# Drvenkar_Dario.net
KiCad netlist of a schematic drawn in Altium Designer
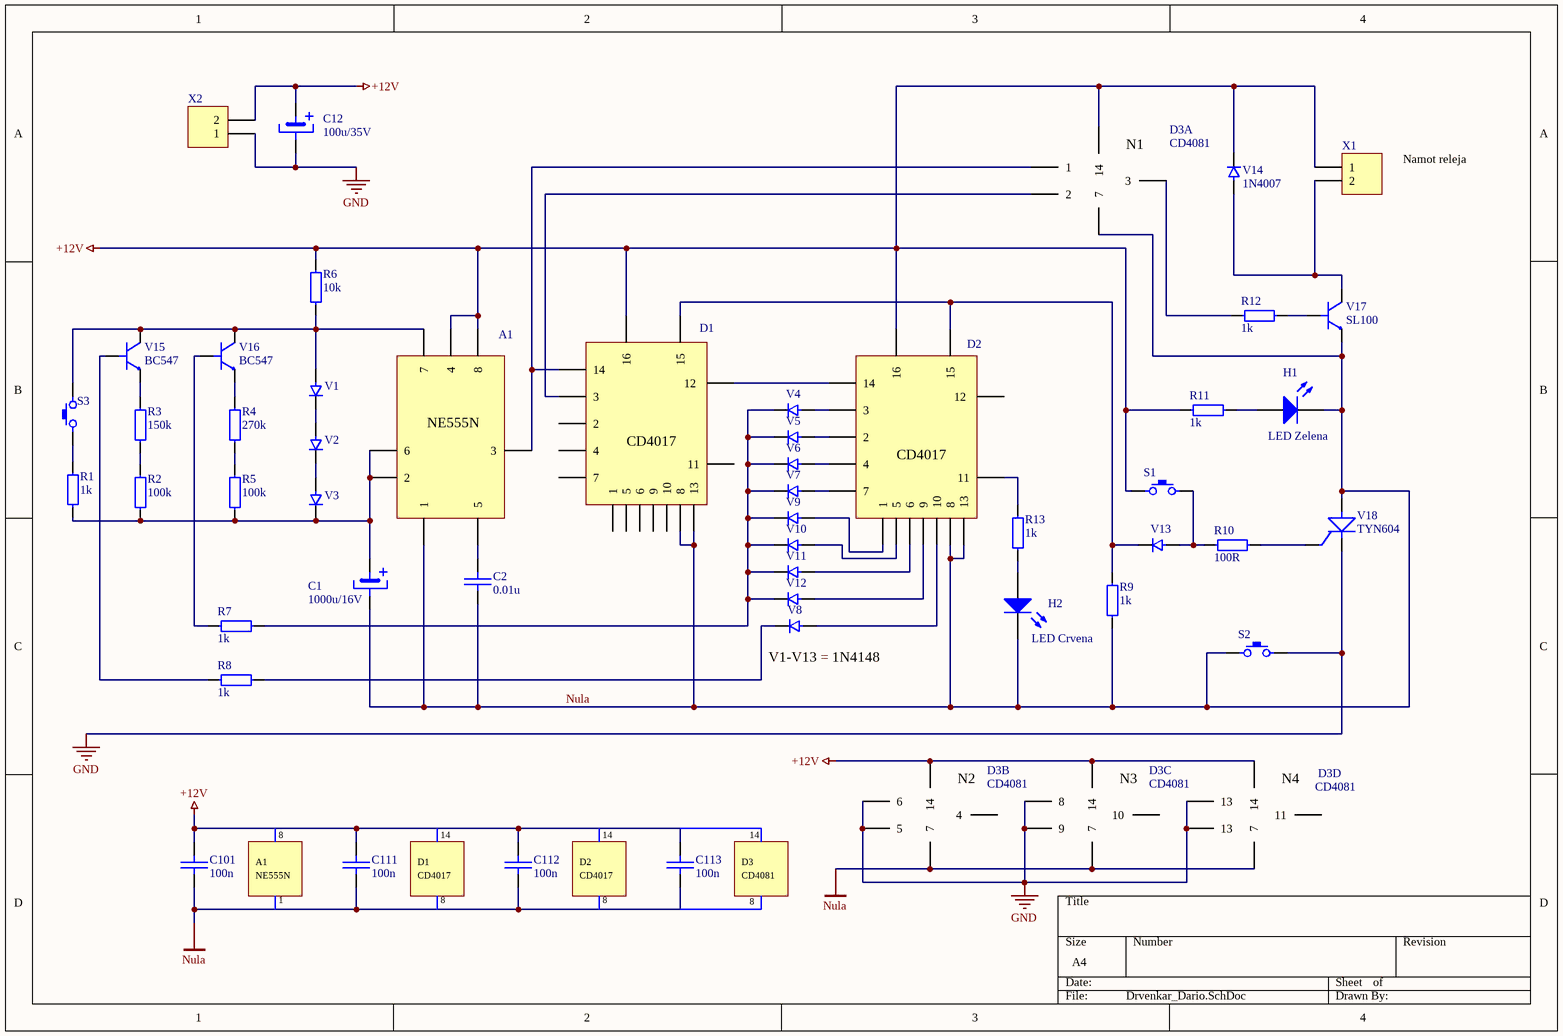
[diagram p0: Drvenkar_Dario.SchDoc]

(export (version "E")
  (design (tool "Eeschema 10.0.6"))
  (components
    (comp (ref "A1") (value "NE555N") (footprint "DIP-8") (libsource (lib "Schlib1") (part "NE555N")))
    (comp (ref "C1") (value "1000u/16V") (footprint "ELKO-10x16") (libsource (lib "Schlib1") (part "ELKO")))
    (comp (ref "C2") (value "0.01u") (footprint "RAD-0.2") (libsource (lib "Schlib1") (part "Kondenzator")))
    (comp (ref "C12")
      (value "100u/35V")
      (footprint "ELKO-6.3x20")
      (libsource (lib "Drvenkar_Dario") (part "ELKO"))
    )
    (comp (ref "C101") (value "100n") (footprint "RAD-0.2") (libsource (lib "Schlib1") (part "Kondenzator")))
    (comp (ref "C111") (value "100n") (footprint "RAD-0.2") (libsource (lib "Schlib1") (part "Kondenzator")))
    (comp (ref "C112") (value "100n") (footprint "RAD-0.2") (libsource (lib "Schlib1") (part "Kondenzator")))
    (comp (ref "C113") (value "100n") (footprint "RAD-0.2") (libsource (lib "Schlib1") (part "Kondenzator")))
    (comp (ref "D1") (value "CD4017") (footprint "DIP-16") (libsource (lib "Drvenkar_Dario") (part "CD4017")))
    (comp (ref "D2") (value "CD4017") (footprint "DIP-16") (libsource (lib "Drvenkar_Dario") (part "CD4017")))
    (comp (ref "D3") (value "CD4081") (footprint "DIP-14") (libsource (lib "Drvenkar_Dario") (part "CD4081")))
    (comp (ref "H1")
      (value "LED Zelena")
      (footprint "LED dioda")
      (description "Typical RED GaAs LED")
      (libsource (lib "Miscellaneous Devices") (part "LED1"))
    )
    (comp (ref "H2")
      (value "LED Crvena")
      (footprint "LED dioda")
      (description "Typical RED, GREEN, YELLOW, AMBER GaAs LED")
      (libsource (lib "Miscellaneous Devices") (part "LED2"))
    )
    (comp (ref "R1") (value "1k") (footprint "AXIAL-0.4") (libsource (lib "Schlib1") (part "Otpornik")))
    (comp (ref "R2") (value "100k") (footprint "AXIAL-0.4") (libsource (lib "Schlib1") (part "Otpornik")))
    (comp (ref "R3") (value "150k") (footprint "AXIAL-0.4") (libsource (lib "Schlib1") (part "Otpornik")))
    (comp (ref "R4") (value "270k") (footprint "AXIAL-0.4") (libsource (lib "Schlib1") (part "Otpornik")))
    (comp (ref "R5") (value "100k") (footprint "AXIAL-0.4") (libsource (lib "Schlib1") (part "Otpornik")))
    (comp (ref "R6") (value "10k") (footprint "AXIAL-0.4") (libsource (lib "Schlib1") (part "Otpornik")))
    (comp (ref "R7") (value "1k") (footprint "AXIAL-0.4") (libsource (lib "Schlib1") (part "Otpornik")))
    (comp (ref "R8") (value "1k") (footprint "AXIAL-0.4") (libsource (lib "Schlib1") (part "Otpornik")))
    (comp (ref "R9") (value "1k") (footprint "AXIAL-0.4") (libsource (lib "Schlib1") (part "Otpornik")))
    (comp (ref "R10") (value "100R") (footprint "AXIAL-0.4") (libsource (lib "Schlib1") (part "Otpornik")))
    (comp (ref "R11") (value "1k") (footprint "AXIAL-0.4") (libsource (lib "Schlib1") (part "Otpornik")))
    (comp (ref "R12") (value "1k") (footprint "AXIAL-0.4") (libsource (lib "Schlib1") (part "Otpornik")))
    (comp (ref "R13") (value "1k") (footprint "AXIAL-0.4") (libsource (lib "Schlib1") (part "Otpornik")))
    (comp (ref "S1") (value "Tipkalo") (footprint "Taster") (libsource (lib "Schlib1") (part "Tipkalo")))
    (comp (ref "S2") (value "Tipkalo") (footprint "Taster") (libsource (lib "Schlib1") (part "Tipkalo")))
    (comp (ref "S3") (value "Tipkalo") (footprint "Taster") (libsource (lib "") (part "Tipkalo_1")))
    (comp (ref "V1") (value "1N4148") (footprint "DIODE-0.4") (libsource (lib "Schlib1") (part "1N4148")))
    (comp (ref "V2") (value "1N4148") (footprint "DIODE-0.4") (libsource (lib "Schlib1") (part "1N4148")))
    (comp (ref "V3") (value "1N4148") (footprint "DIODE-0.4") (libsource (lib "Schlib1") (part "1N4148")))
    (comp (ref "V4") (value "1N4148") (footprint "DIODE-0.4") (libsource (lib "Schlib1") (part "1N4148")))
    (comp (ref "V5") (value "1N4148") (footprint "DIODE-0.4") (libsource (lib "Schlib1") (part "1N4148")))
    (comp (ref "V6") (value "1N4148") (footprint "DIODE-0.4") (libsource (lib "Schlib1") (part "1N4148")))
    (comp (ref "V7") (value "1N4148") (footprint "DIODE-0.4") (libsource (lib "Schlib1") (part "1N4148")))
    (comp (ref "V8") (value "1N4148") (footprint "DIODE-0.4") (libsource (lib "Schlib1") (part "1N4148")))
    (comp (ref "V9") (value "1N4148") (footprint "DIODE-0.4") (libsource (lib "Schlib1") (part "1N4148")))
    (comp (ref "V10") (value "1N4148") (footprint "DIODE-0.4") (libsource (lib "Schlib1") (part "1N4148")))
    (comp (ref "V11") (value "1N4148") (footprint "DIODE-0.4") (libsource (lib "Schlib1") (part "1N4148")))
    (comp (ref "V12") (value "1N4148") (footprint "DIODE-0.4") (libsource (lib "Schlib1") (part "1N4148")))
    (comp (ref "V13") (value "1N4148") (footprint "DIODE-0.4") (libsource (lib "Schlib1") (part "1N4148")))
    (comp (ref "V14") (value "1N4007") (footprint "DIODE-0.4") (libsource (lib "Schlib1") (part "1N4007")))
    (comp (ref "V15") (value "BC547") (footprint "TO-92") (libsource (lib "Schlib1") (part "Tranzistor")))
    (comp (ref "V16") (value "BC547") (footprint "TO-92") (libsource (lib "Schlib1") (part "Tranzistor")))
    (comp (ref "V17") (value "SL100") (footprint "TO-92") (libsource (lib "Schlib1") (part "Tranzistor")))
    (comp (ref "V18") (value "TYN604") (footprint "TO-220-AB") (libsource (lib "Schlib1") (part "Tiristor")))
    (comp (ref "X1")
      (value "2-pinski konektor")
      (footprint "Redna stezaljka")
      (description "Header, 2-Pin")
      (libsource (lib "Miscellaneous Connectors") (part "Header 2"))
    )
    (comp (ref "X2")
      (value "2-pinski konektor")
      (footprint "Redna stezaljka")
      (description "Header, 2-Pin")
      (libsource (lib "") (part "Header 2_1"))
    )
  )
  (nets
    (net (code "1") (name "+12V") (class "Default")
      (node (ref "A1") (pin "4") (pinfunction "4_4") (pintype "passive"))
      (node (ref "A1") (pin "8") (pinfunction "8_8") (pintype "passive"))
      (node (ref "C101") (pin "1") (pinfunction "1_1") (pintype "passive"))
      (node (ref "C111") (pin "1") (pinfunction "1_1") (pintype "passive"))
      (node (ref "C112") (pin "1") (pinfunction "1_1") (pintype "passive"))
      (node (ref "C113") (pin "1") (pinfunction "1_1") (pintype "passive"))
      (node (ref "C12") (pin "1") (pinfunction "1_1") (pintype "passive"))
      (node (ref "D1") (pin "16") (pinfunction "16_16") (pintype "passive"))
      (node (ref "D2") (pin "16") (pinfunction "16_16") (pintype "passive"))
      (node (ref "D3") (pin "14") (pinfunction "14_14") (pintype "passive"))
      (node (ref "R11") (pin "1") (pinfunction "1_1") (pintype "passive"))
      (node (ref "R6") (pin "1") (pinfunction "1_1") (pintype "passive"))
      (node (ref "S1") (pin "2") (pinfunction "2_2") (pintype "passive"))
      (node (ref "V14") (pin "2") (pinfunction "2_2") (pintype "passive"))
      (node (ref "X1") (pin "1") (pinfunction "1_1") (pintype "passive"))
      (node (ref "X2") (pin "2") (pinfunction "2_2") (pintype "passive"))
    )
    (net (code "2") (name "GND") (class "Default")
      (node (ref "C12") (pin "2") (pinfunction "2_2") (pintype "passive"))
      (node (ref "D3") (pin "13") (pinfunction "13_13") (pintype "passive"))
      (node (ref "D3") (pin "5") (pinfunction "5_5") (pintype "passive"))
      (node (ref "D3") (pin "6") (pinfunction "6_6") (pintype "passive"))
      (node (ref "D3") (pin "8") (pinfunction "8_8") (pintype "passive"))
      (node (ref "D3") (pin "9") (pinfunction "9_9") (pintype "passive"))
      (node (ref "S2") (pin "1") (pinfunction "1_1") (pintype "passive"))
      (node (ref "V18") (pin "2") (pinfunction "2_2") (pintype "passive"))
      (node (ref "X2") (pin "1") (pinfunction "1_1") (pintype "passive"))
    )
    (net (code "3") (name "Net-(A1-Pad2)") (class "Default")
      (node (ref "A1") (pin "2") (pinfunction "2_2") (pintype "passive"))
      (node (ref "A1") (pin "6") (pinfunction "6_6") (pintype "passive"))
      (node (ref "C1") (pin "1") (pinfunction "1_1") (pintype "passive"))
      (node (ref "R1") (pin "2") (pinfunction "2_2") (pintype "passive"))
      (node (ref "R2") (pin "2") (pinfunction "2_2") (pintype "passive"))
      (node (ref "R5") (pin "1") (pinfunction "1_1") (pintype "passive"))
      (node (ref "V3") (pin "2") (pinfunction "2_2") (pintype "passive"))
    )
    (net (code "4") (name "Net-(A1-Pad3)") (class "Default")
      (node (ref "A1") (pin "3") (pinfunction "3_3") (pintype "passive"))
      (node (ref "D1") (pin "14") (pinfunction "14_14") (pintype "passive"))
      (node (ref "D3") (pin "1") (pinfunction "1_1") (pintype "passive"))
    )
    (net (code "5") (name "Net-(A1-Pad5)") (class "Default")
      (node (ref "A1") (pin "5") (pinfunction "5_5") (pintype "passive"))
      (node (ref "C2") (pin "2") (pinfunction "2_2") (pintype "passive"))
    )
    (net (code "6") (name "Net-(A1-Pad7)") (class "Default")
      (node (ref "A1") (pin "7") (pinfunction "7_7") (pintype "passive"))
      (node (ref "R6") (pin "2") (pinfunction "2_2") (pintype "passive"))
      (node (ref "S3") (pin "1") (pinfunction "1_1") (pintype "passive"))
      (node (ref "V1") (pin "1") (pinfunction "1_1") (pintype "passive"))
      (node (ref "V15") (pin "3") (pinfunction "3_3") (pintype "passive"))
      (node (ref "V16") (pin "3") (pinfunction "3_3") (pintype "passive"))
    )
    (net (code "7") (name "Net-(D1-Pad3)") (class "Default")
      (node (ref "D1") (pin "3") (pinfunction "3_3") (pintype "passive"))
      (node (ref "D3") (pin "2") (pinfunction "2_2") (pintype "passive"))
    )
    (net (code "8") (name "Net-(D1-Pad12)") (class "Default")
      (node (ref "D1") (pin "12") (pinfunction "12_12") (pintype "passive"))
      (node (ref "D2") (pin "14") (pinfunction "14_14") (pintype "passive"))
    )
    (net (code "9") (name "Net-(D1-Pad15)") (class "Default")
      (node (ref "D1") (pin "15") (pinfunction "15_15") (pintype "passive"))
      (node (ref "D2") (pin "15") (pinfunction "15_15") (pintype "passive"))
      (node (ref "R9") (pin "2") (pinfunction "2_2") (pintype "passive"))
      (node (ref "V13") (pin "2") (pinfunction "2_2") (pintype "passive"))
    )
    (net (code "10") (name "Net-(D2-Pad1)") (class "Default")
      (node (ref "D2") (pin "1") (pinfunction "1_1") (pintype "passive"))
      (node (ref "V9") (pin "1") (pinfunction "1_1") (pintype "passive"))
    )
    (net (code "11") (name "Net-(D2-Pad2)") (class "Default")
      (node (ref "D2") (pin "2") (pinfunction "2_2") (pintype "passive"))
      (node (ref "V5") (pin "1") (pinfunction "1_1") (pintype "passive"))
    )
    (net (code "12") (name "Net-(D2-Pad3)") (class "Default")
      (node (ref "D2") (pin "3") (pinfunction "3_3") (pintype "passive"))
      (node (ref "V4") (pin "1") (pinfunction "1_1") (pintype "passive"))
    )
    (net (code "13") (name "Net-(D2-Pad4)") (class "Default")
      (node (ref "D2") (pin "4") (pinfunction "4_4") (pintype "passive"))
      (node (ref "V6") (pin "1") (pinfunction "1_1") (pintype "passive"))
    )
    (net (code "14") (name "Net-(D2-Pad5)") (class "Default")
      (node (ref "D2") (pin "5") (pinfunction "5_5") (pintype "passive"))
      (node (ref "V10") (pin "1") (pinfunction "1_1") (pintype "passive"))
    )
    (net (code "15") (name "Net-(D2-Pad6)") (class "Default")
      (node (ref "D2") (pin "6") (pinfunction "6_6") (pintype "passive"))
      (node (ref "V11") (pin "1") (pinfunction "1_1") (pintype "passive"))
    )
    (net (code "16") (name "Net-(D2-Pad7)") (class "Default")
      (node (ref "D2") (pin "7") (pinfunction "7_7") (pintype "passive"))
      (node (ref "V7") (pin "1") (pinfunction "1_1") (pintype "passive"))
    )
    (net (code "17") (name "Net-(D2-Pad9)") (class "Default")
      (node (ref "D2") (pin "9") (pinfunction "9_9") (pintype "passive"))
      (node (ref "V12") (pin "1") (pinfunction "1_1") (pintype "passive"))
    )
    (net (code "18") (name "Net-(D2-Pad10)") (class "Default")
      (node (ref "D2") (pin "10") (pinfunction "10_10") (pintype "passive"))
      (node (ref "V8") (pin "1") (pinfunction "1_1") (pintype "passive"))
    )
    (net (code "19") (name "Net-(D2-Pad11)") (class "Default")
      (node (ref "D2") (pin "11") (pinfunction "11_11") (pintype "passive"))
      (node (ref "R13") (pin "1") (pinfunction "1_1") (pintype "passive"))
    )
    (net (code "20") (name "Net-(D3-Pad3)") (class "Default")
      (node (ref "D3") (pin "3") (pinfunction "3_3") (pintype "passive"))
      (node (ref "R12") (pin "1") (pinfunction "1_1") (pintype "passive"))
    )
    (net (code "21") (name "Net-(H1-A)") (class "Default")
      (node (ref "H1") (pin "1") (pinfunction "A_1") (pintype "passive"))
      (node (ref "R11") (pin "2") (pinfunction "2_2") (pintype "passive"))
    )
    (net (code "22") (name "Net-(H2-A)") (class "Default")
      (node (ref "H2") (pin "1") (pinfunction "A_1") (pintype "passive"))
      (node (ref "R13") (pin "2") (pinfunction "2_2") (pintype "passive"))
    )
    (net (code "23") (name "Net-(R1-Pad1)") (class "Default")
      (node (ref "R1") (pin "1") (pinfunction "1_1") (pintype "passive"))
      (node (ref "S3") (pin "2") (pinfunction "2_2") (pintype "passive"))
    )
    (net (code "24") (name "Net-(R2-Pad1)") (class "Default")
      (node (ref "R2") (pin "1") (pinfunction "1_1") (pintype "passive"))
      (node (ref "R3") (pin "2") (pinfunction "2_2") (pintype "passive"))
    )
    (net (code "25") (name "Net-(R3-Pad1)") (class "Default")
      (node (ref "R3") (pin "1") (pinfunction "1_1") (pintype "passive"))
      (node (ref "V15") (pin "2") (pinfunction "2_2") (pintype "passive"))
    )
    (net (code "26") (name "Net-(R4-Pad1)") (class "Default")
      (node (ref "R4") (pin "1") (pinfunction "1_1") (pintype "passive"))
      (node (ref "R5") (pin "2") (pinfunction "2_2") (pintype "passive"))
    )
    (net (code "27") (name "Net-(R4-Pad2)") (class "Default")
      (node (ref "R4") (pin "2") (pinfunction "2_2") (pintype "passive"))
      (node (ref "V16") (pin "2") (pinfunction "2_2") (pintype "passive"))
    )
    (net (code "28") (name "Net-(R7-Pad1)") (class "Default")
      (node (ref "R7") (pin "1") (pinfunction "1_1") (pintype "passive"))
      (node (ref "V16") (pin "1") (pinfunction "1_1") (pintype "passive"))
    )
    (net (code "29") (name "Net-(R7-Pad2)") (class "Default")
      (node (ref "R7") (pin "2") (pinfunction "2_2") (pintype "passive"))
      (node (ref "V10") (pin "2") (pinfunction "2_2") (pintype "passive"))
      (node (ref "V11") (pin "2") (pinfunction "2_2") (pintype "passive"))
      (node (ref "V12") (pin "2") (pinfunction "2_2") (pintype "passive"))
      (node (ref "V4") (pin "2") (pinfunction "2_2") (pintype "passive"))
      (node (ref "V5") (pin "2") (pinfunction "2_2") (pintype "passive"))
      (node (ref "V6") (pin "2") (pinfunction "2_2") (pintype "passive"))
      (node (ref "V7") (pin "2") (pinfunction "2_2") (pintype "passive"))
      (node (ref "V9") (pin "2") (pinfunction "2_2") (pintype "passive"))
    )
    (net (code "30") (name "Net-(R8-Pad1)") (class "Default")
      (node (ref "R8") (pin "1") (pinfunction "1_1") (pintype "passive"))
      (node (ref "V15") (pin "1") (pinfunction "1_1") (pintype "passive"))
    )
    (net (code "31") (name "Net-(R8-Pad2)") (class "Default")
      (node (ref "R8") (pin "2") (pinfunction "2_2") (pintype "passive"))
      (node (ref "V8") (pin "2") (pinfunction "2_2") (pintype "passive"))
    )
    (net (code "32") (name "Net-(R10-Pad1)") (class "Default")
      (node (ref "R10") (pin "1") (pinfunction "1_1") (pintype "passive"))
      (node (ref "S1") (pin "1") (pinfunction "1_1") (pintype "passive"))
      (node (ref "V13") (pin "1") (pinfunction "1_1") (pintype "passive"))
    )
    (net (code "33") (name "Net-(R10-Pad2)") (class "Default")
      (node (ref "R10") (pin "2") (pinfunction "2_2") (pintype "passive"))
      (node (ref "V18") (pin "3") (pinfunction "3_3") (pintype "passive"))
    )
    (net (code "34") (name "Net-(R12-Pad2)") (class "Default")
      (node (ref "R12") (pin "2") (pinfunction "2_2") (pintype "passive"))
      (node (ref "V17") (pin "1") (pinfunction "1_1") (pintype "passive"))
    )
    (net (code "35") (name "Net-(V1-Pad2)") (class "Default")
      (node (ref "V1") (pin "2") (pinfunction "2_2") (pintype "passive"))
      (node (ref "V2") (pin "1") (pinfunction "1_1") (pintype "passive"))
    )
    (net (code "36") (name "Net-(V2-Pad2)") (class "Default")
      (node (ref "V2") (pin "2") (pinfunction "2_2") (pintype "passive"))
      (node (ref "V3") (pin "1") (pinfunction "1_1") (pintype "passive"))
    )
    (net (code "37") (name "Net-(V14-Pad1)") (class "Default")
      (node (ref "V14") (pin "1") (pinfunction "1_1") (pintype "passive"))
      (node (ref "V17") (pin "3") (pinfunction "3_3") (pintype "passive"))
      (node (ref "X1") (pin "2") (pinfunction "2_2") (pintype "passive"))
    )
    (net (code "38") (name "Nula") (class "Default")
      (node (ref "A1") (pin "1") (pinfunction "1_1") (pintype "passive"))
      (node (ref "C1") (pin "2") (pinfunction "2_2") (pintype "passive"))
      (node (ref "C101") (pin "2") (pinfunction "2_2") (pintype "passive"))
      (node (ref "C111") (pin "2") (pinfunction "2_2") (pintype "passive"))
      (node (ref "C112") (pin "2") (pinfunction "2_2") (pintype "passive"))
      (node (ref "C113") (pin "2") (pinfunction "2_2") (pintype "passive"))
      (node (ref "C2") (pin "1") (pinfunction "1_1") (pintype "passive"))
      (node (ref "D1") (pin "13") (pinfunction "13_13") (pintype "passive"))
      (node (ref "D1") (pin "8") (pinfunction "8_8") (pintype "passive"))
      (node (ref "D2") (pin "13") (pinfunction "13_13") (pintype "passive"))
      (node (ref "D2") (pin "8") (pinfunction "8_8") (pintype "passive"))
      (node (ref "D3") (pin "7") (pinfunction "7_7") (pintype "passive"))
      (node (ref "H1") (pin "2") (pinfunction "K_2") (pintype "passive"))
      (node (ref "H2") (pin "2") (pinfunction "K_2") (pintype "passive"))
      (node (ref "R9") (pin "1") (pinfunction "1_1") (pintype "passive"))
      (node (ref "S2") (pin "2") (pinfunction "2_2") (pintype "passive"))
      (node (ref "V17") (pin "2") (pinfunction "2_2") (pintype "passive"))
      (node (ref "V18") (pin "1") (pinfunction "1_1") (pintype "passive"))
    )
    (net (code "39") (name "unconnected-(D1-Pad1)") (class "Default")
      (node (ref "D1") (pin "1") (pinfunction "1_1") (pintype "passive"))
    )
    (net (code "40") (name "unconnected-(D1-Pad2)") (class "Default")
      (node (ref "D1") (pin "2") (pinfunction "2_2") (pintype "passive"))
    )
    (net (code "41") (name "unconnected-(D1-Pad4)") (class "Default")
      (node (ref "D1") (pin "4") (pinfunction "4_4") (pintype "passive"))
    )
    (net (code "42") (name "unconnected-(D1-Pad5)") (class "Default")
      (node (ref "D1") (pin "5") (pinfunction "5_5") (pintype "passive"))
    )
    (net (code "43") (name "unconnected-(D1-Pad6)") (class "Default")
      (node (ref "D1") (pin "6") (pinfunction "6_6") (pintype "passive"))
    )
    (net (code "44") (name "unconnected-(D1-Pad7)") (class "Default")
      (node (ref "D1") (pin "7") (pinfunction "7_7") (pintype "passive"))
    )
    (net (code "45") (name "unconnected-(D1-Pad9)") (class "Default")
      (node (ref "D1") (pin "9") (pinfunction "9_9") (pintype "passive"))
    )
    (net (code "46") (name "unconnected-(D1-Pad10)") (class "Default")
      (node (ref "D1") (pin "10") (pinfunction "10_10") (pintype "passive"))
    )
    (net (code "47") (name "unconnected-(D1-Pad11)") (class "Default")
      (node (ref "D1") (pin "11") (pinfunction "11_11") (pintype "passive"))
    )
    (net (code "48") (name "unconnected-(D2-Pad12)") (class "Default")
      (node (ref "D2") (pin "12") (pinfunction "12_12") (pintype "passive"))
    )
    (net (code "49") (name "unconnected-(D3-Pad4)") (class "Default")
      (node (ref "D3") (pin "4") (pinfunction "4_4") (pintype "passive"))
    )
    (net (code "50") (name "unconnected-(D3-Pad10)") (class "Default")
      (node (ref "D3") (pin "10") (pinfunction "10_10") (pintype "passive"))
    )
    (net (code "51") (name "unconnected-(D3-Pad11)") (class "Default")
      (node (ref "D3") (pin "11") (pinfunction "11_11") (pintype "passive"))
    )
  )
)
